# BYOB-BoosterPack-Template.net
KiCad netlist of a schematic drawn in EAGLE
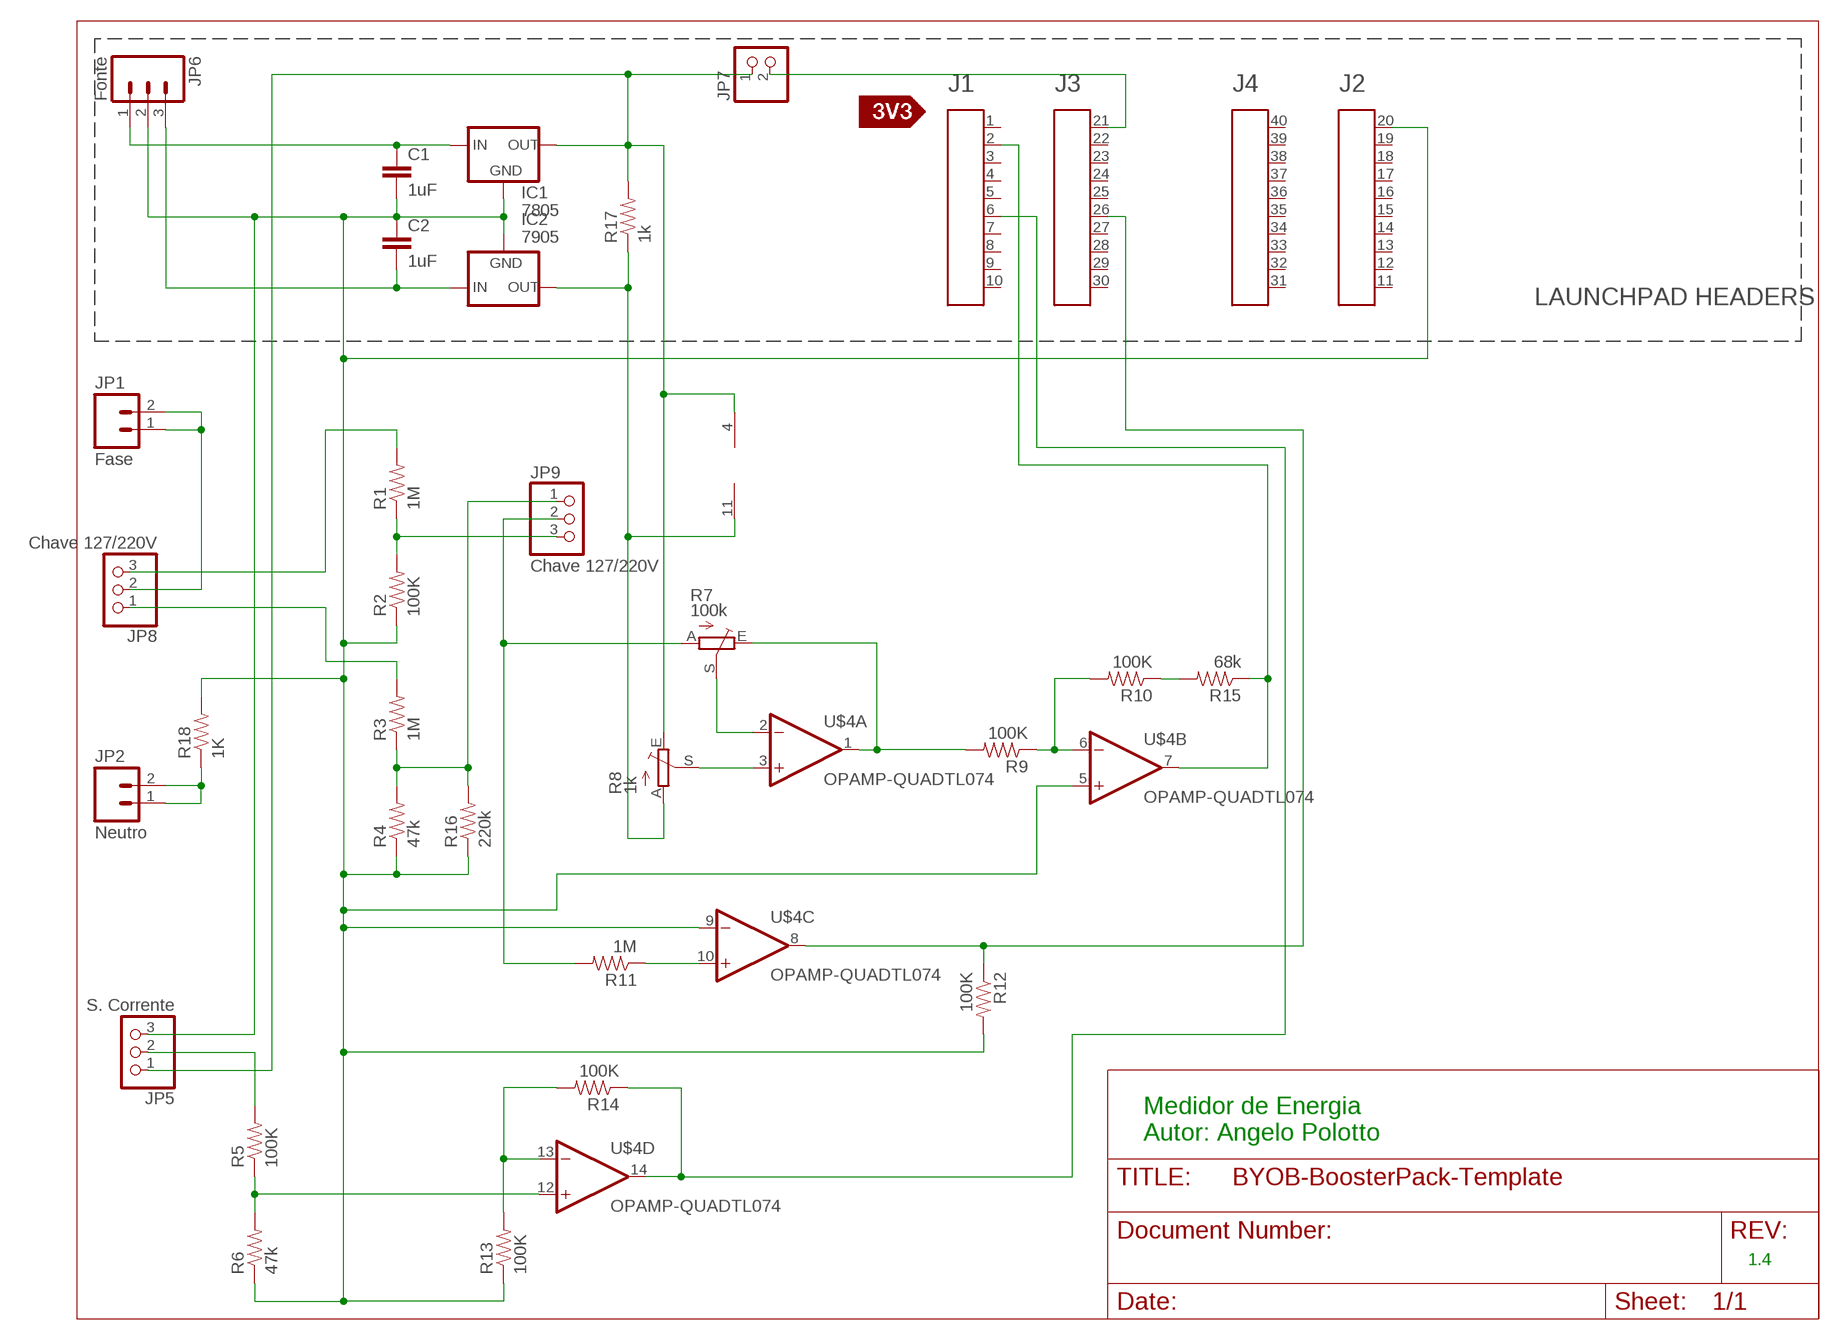
[diagram p0: schematic, sheet 1]

(export (version "E")
  (design (tool "Eeschema 10.0.6"))
  (components
    (comp (ref "A1")
      (value "HEADER4X10-BOOSTERPACK")
      (footprint "eagle-import:4X10-BOOSTERPACK")
      (libsource (lib "eagle-import") (part "HEADER4X10-BOOSTERPACK"))
    )
    (comp (ref "C1")
      (value "1uF")
      (footprint "eagle-import:CAP-PTH-SMALL-KIT")
      (libsource (lib "eagle-import") (part "0.1UF-50V-20%(PTH)KIT-EZ"))
    )
    (comp (ref "C2")
      (value "1uF")
      (footprint "eagle-import:CAP-PTH-SMALL-KIT")
      (libsource (lib "eagle-import") (part "0.1UF-50V-20%(PTH)KIT-EZ"))
    )
    (comp (ref "IC1")
      (value "7805")
      (footprint "eagle-import:78XXS")
      (libsource (lib "eagle-import") (part "78XXS"))
    )
    (comp (ref "IC2")
      (value "7905")
      (footprint "eagle-import:79XXS")
      (libsource (lib "eagle-import") (part "79XXS"))
    )
    (comp (ref "JP1")
      (value "Fase")
      (footprint "eagle-import:1X02_XTRA_BIG")
      (libsource (lib "eagle-import") (part "M02PTH4"))
    )
    (comp (ref "JP2")
      (value "Neutro")
      (footprint "eagle-import:1X02_XTRA_BIG")
      (libsource (lib "eagle-import") (part "M02PTH4"))
    )
    (comp (ref "JP5")
      (value "S. Corrente")
      (footprint "eagle-import:1X03")
      (libsource (lib "eagle-import") (part "PINHD-1X3"))
    )
    (comp (ref "JP6")
      (value "Fonte")
      (footprint "eagle-import:SCREWTERMINAL-5MM-3")
      (libsource (lib "eagle-import") (part "M03-SCREW-5MM"))
    )
    (comp (ref "JP7")
      (value "PINHD-1X2")
      (footprint "eagle-import:1X02")
      (libsource (lib "eagle-import") (part "PINHD-1X2"))
    )
    (comp (ref "JP8")
      (value "Chave 127/220V")
      (footprint "eagle-import:1X03")
      (libsource (lib "eagle-import") (part "PINHD-1X3"))
    )
    (comp (ref "JP9")
      (value "Chave 127/220V")
      (footprint "eagle-import:1X03")
      (libsource (lib "eagle-import") (part "PINHD-1X3"))
    )
    (comp (ref "R1")
      (value "1M")
      (footprint "eagle-import:AXIAL-0.3")
      (libsource (lib "eagle-import") (part "100KOHM-1/4W-1%(PTH)HORIZ"))
    )
    (comp (ref "R2")
      (value "100K")
      (footprint "eagle-import:AXIAL-0.3")
      (libsource (lib "eagle-import") (part "100KOHM-1/4W-1%(PTH)HORIZ"))
    )
    (comp (ref "R3")
      (value "1M")
      (footprint "eagle-import:AXIAL-0.3")
      (libsource (lib "eagle-import") (part "100KOHM-1/4W-1%(PTH)HORIZ"))
    )
    (comp (ref "R4")
      (value "47k")
      (footprint "eagle-import:AXIAL-0.3")
      (libsource (lib "eagle-import") (part "100KOHM-1/4W-1%(PTH)HORIZ"))
    )
    (comp (ref "R5")
      (value "100K")
      (footprint "eagle-import:AXIAL-0.3")
      (libsource (lib "eagle-import") (part "100KOHM-1/4W-1%(PTH)HORIZ"))
    )
    (comp (ref "R6")
      (value "47k")
      (footprint "eagle-import:AXIAL-0.3")
      (libsource (lib "eagle-import") (part "100KOHM-1/4W-1%(PTH)HORIZ"))
    )
    (comp (ref "R7")
      (value "100k")
      (footprint "eagle-import:B64Y")
      (libsource (lib "eagle-import") (part "TRIM_EU-B64Y"))
    )
    (comp (ref "R8")
      (value "1k")
      (footprint "eagle-import:B64Y")
      (libsource (lib "eagle-import") (part "TRIM_EU-B64Y"))
    )
    (comp (ref "R9")
      (value "100K")
      (footprint "eagle-import:AXIAL-0.3")
      (libsource (lib "eagle-import") (part "100KOHM-1/4W-1%(PTH)HORIZ"))
    )
    (comp (ref "R10")
      (value "100K")
      (footprint "eagle-import:AXIAL-0.3")
      (libsource (lib "eagle-import") (part "100KOHM-1/4W-1%(PTH)HORIZ"))
    )
    (comp (ref "R11")
      (value "1M")
      (footprint "eagle-import:AXIAL-0.3")
      (libsource (lib "eagle-import") (part "100KOHM-1/4W-1%(PTH)HORIZ"))
    )
    (comp (ref "R12")
      (value "100K")
      (footprint "eagle-import:AXIAL-0.3")
      (libsource (lib "eagle-import") (part "100KOHM-1/4W-1%(PTH)HORIZ"))
    )
    (comp (ref "R13")
      (value "100K")
      (footprint "eagle-import:AXIAL-0.3")
      (libsource (lib "eagle-import") (part "100KOHM-1/4W-1%(PTH)HORIZ"))
    )
    (comp (ref "R14")
      (value "100K")
      (footprint "eagle-import:AXIAL-0.3")
      (libsource (lib "eagle-import") (part "100KOHM-1/4W-1%(PTH)HORIZ"))
    )
    (comp (ref "R15")
      (value "68k")
      (footprint "eagle-import:AXIAL-0.3")
      (libsource (lib "eagle-import") (part "100KOHM-1/4W-1%(PTH)HORIZ"))
    )
    (comp (ref "R16")
      (value "220k")
      (footprint "eagle-import:AXIAL-0.3")
      (libsource (lib "eagle-import") (part "100KOHM-1/4W-1%(PTH)HORIZ"))
    )
    (comp (ref "R17")
      (value "1k")
      (footprint "eagle-import:AXIAL-0.3")
      (libsource (lib "eagle-import") (part "100KOHM-1/4W-1%(PTH)HORIZ"))
    )
    (comp (ref "R18")
      (value "1K")
      (footprint "eagle-import:AXIAL-0.3")
      (libsource (lib "eagle-import") (part "100KOHM-1/4W-1%(PTH)HORIZ"))
    )
    (comp (ref "U$3")
      (value "SILK_3V3_TAG")
      (footprint "eagle-import:SILK_3V3_TAG")
      (libsource (lib "eagle-import") (part "SILK_3V3_TAG"))
    )
    (comp (ref "U$4")
      (value "OPAMP-QUADTL074")
      (footprint "eagle-import:DIP14")
      (libsource (lib "eagle-import") (part "OPAMP-QUADTL074"))
    )
  )
  (nets
    (net (code "1") (name "Net-(A1-P$2)") (class "Default")
      (node (ref "A1") (pin "2") (pinfunction "P$2_2") (pintype "bidirectional"))
      (node (ref "R15") (pin "P$1") (pinfunction "1_P$1") (pintype "passive"))
      (node (ref "U$4") (pin "7") (pinfunction "OUT_7") (pintype "output"))
    )
    (net (code "2") (name "Net-(A1-P$6)") (class "Default")
      (node (ref "A1") (pin "6") (pinfunction "P$6_6") (pintype "bidirectional"))
      (node (ref "R14") (pin "P$1") (pinfunction "1_P$1") (pintype "passive"))
      (node (ref "U$4") (pin "14") (pinfunction "OUT_14") (pintype "output"))
    )
    (net (code "3") (name "Net-(A1-P$20)") (class "Default")
      (node (ref "A1") (pin "20") (pinfunction "P$20_20") (pintype "bidirectional"))
      (node (ref "C1") (pin "2") (pinfunction "2_2") (pintype "passive"))
      (node (ref "C2") (pin "1") (pinfunction "1_1") (pintype "passive"))
      (node (ref "IC1") (pin "GND") (pinfunction "GND_GND") (pintype "input"))
      (node (ref "IC2") (pin "GND") (pinfunction "GND_GND") (pintype "input"))
      (node (ref "JP5") (pin "3") (pinfunction "3_3") (pintype "passive"))
      (node (ref "JP6") (pin "2") (pinfunction "2_2") (pintype "passive"))
      (node (ref "R12") (pin "P$2") (pinfunction "2_P$2") (pintype "passive"))
      (node (ref "R13") (pin "P$1") (pinfunction "1_P$1") (pintype "passive"))
      (node (ref "R16") (pin "P$1") (pinfunction "1_P$1") (pintype "passive"))
      (node (ref "R18") (pin "P$2") (pinfunction "2_P$2") (pintype "passive"))
      (node (ref "R2") (pin "P$1") (pinfunction "1_P$1") (pintype "passive"))
      (node (ref "R4") (pin "P$1") (pinfunction "1_P$1") (pintype "passive"))
      (node (ref "R6") (pin "P$1") (pinfunction "1_P$1") (pintype "passive"))
      (node (ref "U$4") (pin "5") (pinfunction "IN+_5") (pintype "input"))
      (node (ref "U$4") (pin "9") (pinfunction "IN-_9") (pintype "input"))
    )
    (net (code "4") (name "Net-(A1-P$21)") (class "Default")
      (node (ref "A1") (pin "21") (pinfunction "P$21_21") (pintype "bidirectional"))
      (node (ref "JP7") (pin "2") (pinfunction "2_2") (pintype "passive"))
    )
    (net (code "5") (name "Net-(A1-P$26)") (class "Default")
      (node (ref "A1") (pin "26") (pinfunction "P$26_26") (pintype "bidirectional"))
      (node (ref "R12") (pin "P$1") (pinfunction "1_P$1") (pintype "passive"))
      (node (ref "U$4") (pin "8") (pinfunction "OUT_8") (pintype "output"))
    )
    (net (code "6") (name "Net-(C1-Pad1)") (class "Default")
      (node (ref "C1") (pin "1") (pinfunction "1_1") (pintype "passive"))
      (node (ref "IC1") (pin "IN") (pinfunction "IN_IN") (pintype "input"))
      (node (ref "JP6") (pin "1") (pinfunction "1_1") (pintype "passive"))
    )
    (net (code "7") (name "Net-(C2-Pad2)") (class "Default")
      (node (ref "C2") (pin "2") (pinfunction "2_2") (pintype "passive"))
      (node (ref "IC2") (pin "IN") (pinfunction "IN_IN") (pintype "input"))
      (node (ref "JP6") (pin "3") (pinfunction "3_3") (pintype "passive"))
    )
    (net (code "8") (name "Net-(JP1-Pad1)") (class "Default")
      (node (ref "JP1") (pin "1") (pinfunction "1_1") (pintype "passive"))
      (node (ref "JP1") (pin "2") (pinfunction "2_2") (pintype "passive"))
      (node (ref "JP8") (pin "2") (pinfunction "2_2") (pintype "passive"))
    )
    (net (code "9") (name "Net-(R1-1)") (class "Default")
      (node (ref "JP9") (pin "3") (pinfunction "3_3") (pintype "passive"))
      (node (ref "R1") (pin "P$1") (pinfunction "1_P$1") (pintype "passive"))
      (node (ref "R2") (pin "P$2") (pinfunction "2_P$2") (pintype "passive"))
    )
    (net (code "10") (name "Net-(R1-2)") (class "Default")
      (node (ref "JP8") (pin "3") (pinfunction "3_3") (pintype "passive"))
      (node (ref "R1") (pin "P$2") (pinfunction "2_P$2") (pintype "passive"))
    )
    (net (code "11") (name "Net-(R3-2)") (class "Default")
      (node (ref "JP8") (pin "1") (pinfunction "1_1") (pintype "passive"))
      (node (ref "R3") (pin "P$2") (pinfunction "2_P$2") (pintype "passive"))
    )
    (net (code "12") (name "Net-(R5-1)") (class "Default")
      (node (ref "R5") (pin "P$1") (pinfunction "1_P$1") (pintype "passive"))
      (node (ref "R6") (pin "P$2") (pinfunction "2_P$2") (pintype "passive"))
      (node (ref "U$4") (pin "12") (pinfunction "IN+_12") (pintype "input"))
    )
    (net (code "13") (name "Net-(R5-2)") (class "Default")
      (node (ref "JP5") (pin "2") (pinfunction "2_2") (pintype "passive"))
      (node (ref "R5") (pin "P$2") (pinfunction "2_P$2") (pintype "passive"))
    )
    (net (code "14") (name "Net-(R9-2)") (class "Default")
      (node (ref "R7") (pin "E") (pinfunction "E_E") (pintype "passive"))
      (node (ref "R9") (pin "P$2") (pinfunction "2_P$2") (pintype "passive"))
      (node (ref "U$4") (pin "1") (pinfunction "OUT_1") (pintype "output"))
    )
    (net (code "15") (name "Net-(R10-1)") (class "Default")
      (node (ref "R10") (pin "P$1") (pinfunction "1_P$1") (pintype "passive"))
      (node (ref "R15") (pin "P$2") (pinfunction "2_P$2") (pintype "passive"))
    )
    (net (code "16") (name "Net-(R10-2)") (class "Default")
      (node (ref "R10") (pin "P$2") (pinfunction "2_P$2") (pintype "passive"))
      (node (ref "R9") (pin "P$1") (pinfunction "1_P$1") (pintype "passive"))
      (node (ref "U$4") (pin "6") (pinfunction "IN-_6") (pintype "input"))
    )
    (net (code "17") (name "Net-(R11-1)") (class "Default")
      (node (ref "R11") (pin "P$1") (pinfunction "1_P$1") (pintype "passive"))
      (node (ref "U$4") (pin "10") (pinfunction "IN+_10") (pintype "input"))
    )
    (net (code "18") (name "Net-(R11-2)") (class "Default")
      (node (ref "JP9") (pin "2") (pinfunction "2_2") (pintype "passive"))
      (node (ref "R11") (pin "P$2") (pinfunction "2_P$2") (pintype "passive"))
      (node (ref "R7") (pin "A") (pinfunction "A_A") (pintype "passive"))
    )
    (net (code "19") (name "Net-(R13-2)") (class "Default")
      (node (ref "R13") (pin "P$2") (pinfunction "2_P$2") (pintype "passive"))
      (node (ref "R14") (pin "P$2") (pinfunction "2_P$2") (pintype "passive"))
      (node (ref "U$4") (pin "13") (pinfunction "IN-_13") (pintype "input"))
    )
    (net (code "20") (name "Net-(R16-2)") (class "Default")
      (node (ref "JP9") (pin "1") (pinfunction "1_1") (pintype "passive"))
      (node (ref "R16") (pin "P$2") (pinfunction "2_P$2") (pintype "passive"))
      (node (ref "R3") (pin "P$1") (pinfunction "1_P$1") (pintype "passive"))
      (node (ref "R4") (pin "P$2") (pinfunction "2_P$2") (pintype "passive"))
    )
    (net (code "21") (name "Net-(R17-1)") (class "Default")
      (node (ref "IC2") (pin "OUT") (pinfunction "OUT_OUT") (pintype "passive"))
      (node (ref "R17") (pin "P$1") (pinfunction "1_P$1") (pintype "passive"))
      (node (ref "R8") (pin "A") (pinfunction "A_A") (pintype "passive"))
      (node (ref "U$4") (pin "11") (pinfunction "VEE_11") (pintype "power_in"))
    )
    (net (code "22") (name "Net-(R17-2)") (class "Default")
      (node (ref "IC1") (pin "OUT") (pinfunction "OUT_OUT") (pintype "passive"))
      (node (ref "JP5") (pin "1") (pinfunction "1_1") (pintype "passive"))
      (node (ref "JP7") (pin "1") (pinfunction "1_1") (pintype "passive"))
      (node (ref "R17") (pin "P$2") (pinfunction "2_P$2") (pintype "passive"))
      (node (ref "R8") (pin "E") (pinfunction "E_E") (pintype "passive"))
      (node (ref "U$4") (pin "4") (pinfunction "VCC_4") (pintype "power_in"))
    )
    (net (code "23") (name "Net-(R18-1)") (class "Default")
      (node (ref "JP2") (pin "1") (pinfunction "1_1") (pintype "passive"))
      (node (ref "JP2") (pin "2") (pinfunction "2_2") (pintype "passive"))
      (node (ref "R18") (pin "P$1") (pinfunction "1_P$1") (pintype "passive"))
    )
    (net (code "24") (name "Net-(U$4A-IN+)") (class "Default")
      (node (ref "R8") (pin "S") (pinfunction "S_S") (pintype "passive"))
      (node (ref "U$4") (pin "3") (pinfunction "IN+_3") (pintype "input"))
    )
    (net (code "25") (name "Net-(U$4A-IN-)") (class "Default")
      (node (ref "R7") (pin "S") (pinfunction "S_S") (pintype "passive"))
      (node (ref "U$4") (pin "2") (pinfunction "IN-_2") (pintype "input"))
    )
    (net (code "26") (name "unconnected-(A1-P$1-Pad1)") (class "Default")
      (node (ref "A1") (pin "1") (pinfunction "P$1_1") (pintype "bidirectional"))
    )
    (net (code "27") (name "unconnected-(A1-P$3-Pad3)") (class "Default")
      (node (ref "A1") (pin "3") (pinfunction "P$3_3") (pintype "bidirectional"))
    )
    (net (code "28") (name "unconnected-(A1-P$4-Pad4)") (class "Default")
      (node (ref "A1") (pin "4") (pinfunction "P$4_4") (pintype "bidirectional"))
    )
    (net (code "29") (name "unconnected-(A1-P$5-Pad5)") (class "Default")
      (node (ref "A1") (pin "5") (pinfunction "P$5_5") (pintype "bidirectional"))
    )
    (net (code "30") (name "unconnected-(A1-P$7-Pad7)") (class "Default")
      (node (ref "A1") (pin "7") (pinfunction "P$7_7") (pintype "bidirectional"))
    )
    (net (code "31") (name "unconnected-(A1-P$8-Pad8)") (class "Default")
      (node (ref "A1") (pin "8") (pinfunction "P$8_8") (pintype "bidirectional"))
    )
    (net (code "32") (name "unconnected-(A1-P$9-Pad9)") (class "Default")
      (node (ref "A1") (pin "9") (pinfunction "P$9_9") (pintype "bidirectional"))
    )
    (net (code "33") (name "unconnected-(A1-P$10-Pad10)") (class "Default")
      (node (ref "A1") (pin "10") (pinfunction "P$10_10") (pintype "bidirectional"))
    )
    (net (code "34") (name "unconnected-(A1-P$11-Pad11)") (class "Default")
      (node (ref "A1") (pin "11") (pinfunction "P$11_11") (pintype "bidirectional"))
    )
    (net (code "35") (name "unconnected-(A1-P$12-Pad12)") (class "Default")
      (node (ref "A1") (pin "12") (pinfunction "P$12_12") (pintype "bidirectional"))
    )
    (net (code "36") (name "unconnected-(A1-P$13-Pad13)") (class "Default")
      (node (ref "A1") (pin "13") (pinfunction "P$13_13") (pintype "bidirectional"))
    )
    (net (code "37") (name "unconnected-(A1-P$14-Pad14)") (class "Default")
      (node (ref "A1") (pin "14") (pinfunction "P$14_14") (pintype "bidirectional"))
    )
    (net (code "38") (name "unconnected-(A1-P$15-Pad15)") (class "Default")
      (node (ref "A1") (pin "15") (pinfunction "P$15_15") (pintype "bidirectional"))
    )
    (net (code "39") (name "unconnected-(A1-P$16-Pad16)") (class "Default")
      (node (ref "A1") (pin "16") (pinfunction "P$16_16") (pintype "bidirectional"))
    )
    (net (code "40") (name "unconnected-(A1-P$17-Pad17)") (class "Default")
      (node (ref "A1") (pin "17") (pinfunction "P$17_17") (pintype "bidirectional"))
    )
    (net (code "41") (name "unconnected-(A1-P$18-Pad18)") (class "Default")
      (node (ref "A1") (pin "18") (pinfunction "P$18_18") (pintype "bidirectional"))
    )
    (net (code "42") (name "unconnected-(A1-P$19-Pad19)") (class "Default")
      (node (ref "A1") (pin "19") (pinfunction "P$19_19") (pintype "bidirectional"))
    )
    (net (code "43") (name "unconnected-(A1-P$22-Pad22)") (class "Default")
      (node (ref "A1") (pin "22") (pinfunction "P$22_22") (pintype "bidirectional"))
    )
    (net (code "44") (name "unconnected-(A1-P$23-Pad23)") (class "Default")
      (node (ref "A1") (pin "23") (pinfunction "P$23_23") (pintype "bidirectional"))
    )
    (net (code "45") (name "unconnected-(A1-P$24-Pad24)") (class "Default")
      (node (ref "A1") (pin "24") (pinfunction "P$24_24") (pintype "bidirectional"))
    )
    (net (code "46") (name "unconnected-(A1-P$25-Pad25)") (class "Default")
      (node (ref "A1") (pin "25") (pinfunction "P$25_25") (pintype "bidirectional"))
    )
    (net (code "47") (name "unconnected-(A1-P$27-Pad27)") (class "Default")
      (node (ref "A1") (pin "27") (pinfunction "P$27_27") (pintype "bidirectional"))
    )
    (net (code "48") (name "unconnected-(A1-P$28-Pad28)") (class "Default")
      (node (ref "A1") (pin "28") (pinfunction "P$28_28") (pintype "bidirectional"))
    )
    (net (code "49") (name "unconnected-(A1-P$29-Pad29)") (class "Default")
      (node (ref "A1") (pin "29") (pinfunction "P$29_29") (pintype "bidirectional"))
    )
    (net (code "50") (name "unconnected-(A1-P$30-Pad30)") (class "Default")
      (node (ref "A1") (pin "30") (pinfunction "P$30_30") (pintype "bidirectional"))
    )
    (net (code "51") (name "unconnected-(A1-P$31-Pad31)") (class "Default")
      (node (ref "A1") (pin "31") (pinfunction "P$31_31") (pintype "bidirectional"))
    )
    (net (code "52") (name "unconnected-(A1-P$32-Pad32)") (class "Default")
      (node (ref "A1") (pin "32") (pinfunction "P$32_32") (pintype "bidirectional"))
    )
    (net (code "53") (name "unconnected-(A1-P$33-Pad33)") (class "Default")
      (node (ref "A1") (pin "33") (pinfunction "P$33_33") (pintype "bidirectional"))
    )
    (net (code "54") (name "unconnected-(A1-P$34-Pad34)") (class "Default")
      (node (ref "A1") (pin "34") (pinfunction "P$34_34") (pintype "bidirectional"))
    )
    (net (code "55") (name "unconnected-(A1-P$35-Pad35)") (class "Default")
      (node (ref "A1") (pin "35") (pinfunction "P$35_35") (pintype "bidirectional"))
    )
    (net (code "56") (name "unconnected-(A1-P$36-Pad36)") (class "Default")
      (node (ref "A1") (pin "36") (pinfunction "P$36_36") (pintype "bidirectional"))
    )
    (net (code "57") (name "unconnected-(A1-P$37-Pad37)") (class "Default")
      (node (ref "A1") (pin "37") (pinfunction "P$37_37") (pintype "bidirectional"))
    )
    (net (code "58") (name "unconnected-(A1-P$38-Pad38)") (class "Default")
      (node (ref "A1") (pin "38") (pinfunction "P$38_38") (pintype "bidirectional"))
    )
    (net (code "59") (name "unconnected-(A1-P$39-Pad39)") (class "Default")
      (node (ref "A1") (pin "39") (pinfunction "P$39_39") (pintype "bidirectional"))
    )
    (net (code "60") (name "unconnected-(A1-P$40-Pad40)") (class "Default")
      (node (ref "A1") (pin "40") (pinfunction "P$40_40") (pintype "bidirectional"))
    )
  )
)
